# 03_Power.net
KiCad netlist of a schematic drawn in Altium Designer
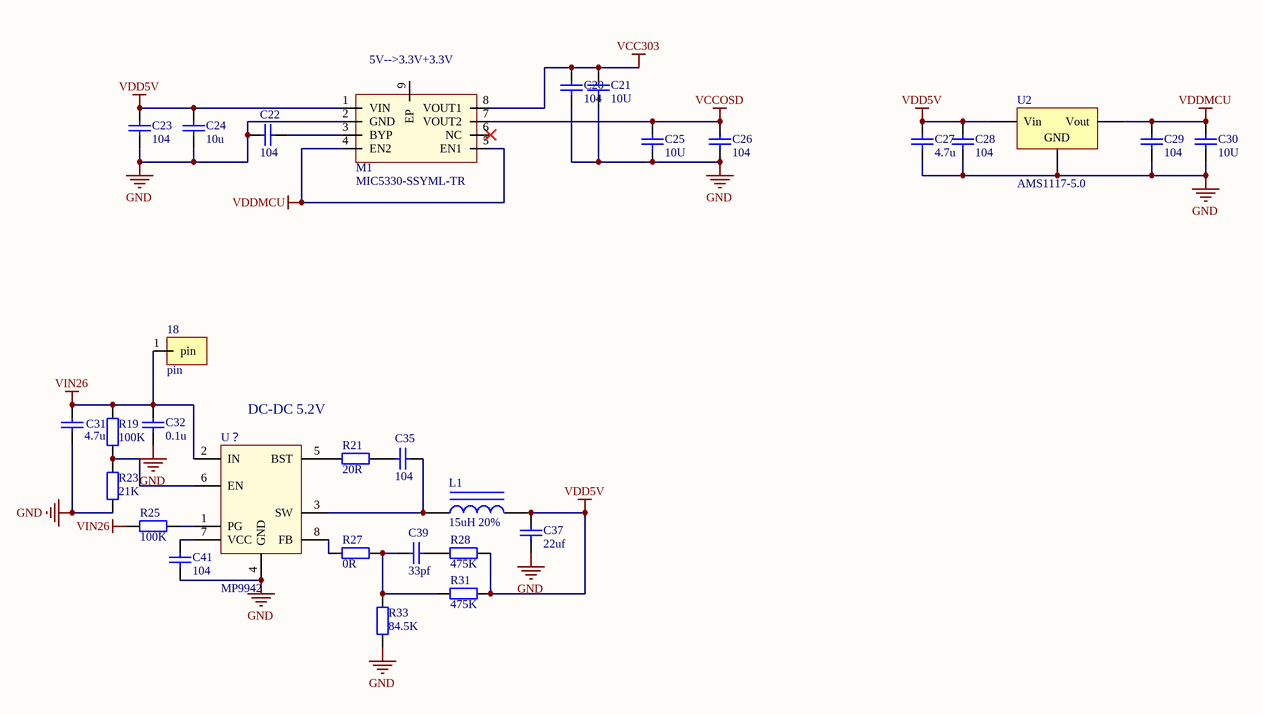
[diagram p0: 03_Power.SchDoc]

(export (version "E")
  (design (tool "Eeschema 10.0.6"))
  (components
    (comp (ref "18") (value "pin") (footprint "DIAN_0.5-1.0") (libsource (lib "My_schlib") (part "dian")))
    (comp (ref "C20")
      (value "104")
      (footprint "0402_C")
      (description "贴片电容")
      (libsource (lib "Miscellaneous Devices LC") (part "0402 100nF (104) 10% 16V"))
    )
    (comp (ref "C21")
      (value "10U")
      (footprint "0603_C")
      (description "贴片电容")
      (libsource (lib "Miscellaneous Devices LC") (part "0603 100nF (104) 10% 50V"))
    )
    (comp (ref "C22")
      (value "104")
      (footprint "0603_C")
      (description "贴片电容")
      (libsource (lib "Miscellaneous Devices LC") (part "0603 100nF (104) 10% 50V"))
    )
    (comp (ref "C23")
      (value "104")
      (footprint "0603_C")
      (description "贴片电容")
      (libsource (lib "Miscellaneous Devices LC") (part "0603 100nF (104) 10% 50V"))
    )
    (comp (ref "C24")
      (value "10u")
      (footprint "0603_C")
      (description "贴片电容")
      (libsource (lib "Miscellaneous Devices LC") (part "0603 100nF (104) 10% 50V"))
    )
    (comp (ref "C25")
      (value "10U")
      (footprint "0603_C")
      (description "贴片电容")
      (libsource (lib "Miscellaneous Devices LC") (part "0603 100nF (104) 10% 50V"))
    )
    (comp (ref "C26")
      (value "104")
      (footprint "0402_C")
      (description "贴片电容")
      (libsource (lib "Miscellaneous Devices LC") (part "0402 100nF (104) 10% 16V"))
    )
    (comp (ref "C27")
      (value "4.7u")
      (footprint "0603_C")
      (description "贴片电容")
      (libsource (lib "Miscellaneous Devices LC") (part "0603 100nF (104) 10% 50V"))
    )
    (comp (ref "C28")
      (value "104")
      (footprint "0603_C")
      (description "贴片电容")
      (libsource (lib "Miscellaneous Devices LC") (part "0603 100nF (104) 10% 50V"))
    )
    (comp (ref "C29")
      (value "104")
      (footprint "0402_C")
      (description "贴片电容")
      (libsource (lib "Miscellaneous Devices LC") (part "0402 100nF (104) 10% 16V"))
    )
    (comp (ref "C30")
      (value "10U")
      (footprint "0603_C")
      (description "贴片电容")
      (libsource (lib "Miscellaneous Devices LC") (part "0603 100nF (104) 10% 50V"))
    )
    (comp (ref "C31")
      (value "4.7u")
      (footprint "0603_C")
      (description "贴片电容")
      (libsource (lib "Miscellaneous Devices LC") (part "0603 100nF (104) 10% 50V"))
    )
    (comp (ref "C32")
      (value "0.1u")
      (footprint "0402_C")
      (description "贴片电容")
      (libsource (lib "Miscellaneous Devices LC") (part "0402 10nF (103) 10% 50V"))
    )
    (comp (ref "C35")
      (value "104")
      (footprint "0402_C")
      (description "贴片电容")
      (libsource (lib "Miscellaneous Devices LC") (part "0402 10nF (103) 10% 50V"))
    )
    (comp (ref "C37")
      (value "22uf")
      (footprint "1206_C")
      (description "贴片电容")
      (libsource (lib "Miscellaneous Devices LC") (part "1206 100nF (104) 10% 50V"))
    )
    (comp (ref "C39")
      (value "33pf")
      (footprint "0402_C")
      (description "贴片电容")
      (libsource (lib "Miscellaneous Devices LC") (part "0402 10nF (103) 10% 50V"))
    )
    (comp (ref "C41")
      (value "104")
      (footprint "0402_C")
      (description "贴片电容")
      (libsource (lib "Miscellaneous Devices LC") (part "0402 10nF (103) 10% 50V"))
    )
    (comp (ref "L1")
      (value "15uH 20%")
      (footprint "0530-L")
      (description "贴片电感")
      (libsource (lib "Miscellaneous Devices LC") (part "0402 15nH 5%"))
    )
    (comp (ref "M1")
      (value "MIC5330-SSYML-TR")
      (footprint "MIC5330-SSYML-TR")
      (description "LDO")
      (libsource (lib "My_schlib") (part "MIC5330-SSYML-TR"))
    )
    (comp (ref "R19")
      (value "100K")
      (footprint "0402_R")
      (description "贴片电阻")
      (libsource (lib "Miscellaneous Devices LC") (part "0402 10KΩ (1002) 1%"))
    )
    (comp (ref "R21")
      (value "20R")
      (footprint "0402_R")
      (description "贴片电阻")
      (libsource (lib "") (part "0402 10KΩ (1002) 1%_2"))
    )
    (comp (ref "R23")
      (value "21K")
      (footprint "0402_R")
      (description "贴片电阻")
      (libsource (lib "Miscellaneous Devices LC") (part "0402 10KΩ (1002) 1%"))
    )
    (comp (ref "R25")
      (value "100K")
      (footprint "0402_R")
      (description "贴片电阻")
      (libsource (lib "") (part "0402 10KΩ (1002) 1%_2"))
    )
    (comp (ref "R27")
      (value "0R")
      (footprint "0402_R")
      (description "贴片电阻")
      (libsource (lib "") (part "0402 10KΩ (1002) 1%_2"))
    )
    (comp (ref "R28")
      (value "475K")
      (footprint "0402_R")
      (description "贴片电阻")
      (libsource (lib "") (part "0402 10KΩ (1002) 1%_2"))
    )
    (comp (ref "R31")
      (value "475K")
      (footprint "0402_R")
      (description "贴片电阻")
      (libsource (lib "") (part "0402 10KΩ (1002) 1%_3"))
    )
    (comp (ref "R33")
      (value "84.5K")
      (footprint "0402_R")
      (description "贴片电阻")
      (libsource (lib "") (part "0402 10KΩ (1002) 1%_1"))
    )
    (comp (ref "U2")
      (value "AMS1117-5.0")
      (footprint "SOT-223")
      (description "低压差线性稳压(LDO)")
      (libsource (lib "Miscellaneous Devices LC") (part "SOT-223 AMS1117-5.0"))
    )
    (comp (ref "U？")
      (value "MP9942")
      (footprint "SOT23-8L")
      (description "DC-DC 2A 4-36V")
      (libsource (lib "My_schlib") (part "MP9942"))
    )
  )
  (nets
    (net (code "1") (name "GND") (class "Default")
      (node (ref "C20") (pin "1") (pinfunction "1_1") (pintype "passive"))
      (node (ref "C21") (pin "2") (pinfunction "2_2") (pintype "passive"))
      (node (ref "C22") (pin "2") (pinfunction "2_2") (pintype "passive"))
      (node (ref "C23") (pin "1") (pinfunction "1_1") (pintype "passive"))
      (node (ref "C24") (pin "1") (pinfunction "1_1") (pintype "passive"))
      (node (ref "C25") (pin "2") (pinfunction "2_2") (pintype "passive"))
      (node (ref "C26") (pin "1") (pinfunction "1_1") (pintype "passive"))
      (node (ref "C27") (pin "2") (pinfunction "2_2") (pintype "passive"))
      (node (ref "C28") (pin "1") (pinfunction "1_1") (pintype "passive"))
      (node (ref "C29") (pin "1") (pinfunction "1_1") (pintype "passive"))
      (node (ref "C30") (pin "2") (pinfunction "2_2") (pintype "passive"))
      (node (ref "C31") (pin "1") (pinfunction "1_1") (pintype "passive"))
      (node (ref "C32") (pin "1") (pinfunction "1_1") (pintype "passive"))
      (node (ref "C37") (pin "1") (pinfunction "1_1") (pintype "passive"))
      (node (ref "C41") (pin "1") (pinfunction "1_1") (pintype "passive"))
      (node (ref "M1") (pin "2") (pinfunction "GND_2") (pintype "passive"))
      (node (ref "R23") (pin "1") (pinfunction "1_1") (pintype "passive"))
      (node (ref "R33") (pin "2") (pinfunction "2_2") (pintype "passive"))
      (node (ref "U2") (pin "1") (pinfunction "GND_1") (pintype "passive"))
      (node (ref "U？") (pin "4") (pinfunction "GND_4") (pintype "passive"))
    )
    (net (code "2") (name "Net-(C35-Pad2)") (class "Default")
      (node (ref "C35") (pin "2") (pinfunction "2_2") (pintype "passive"))
      (node (ref "R21") (pin "1") (pinfunction "1_1") (pintype "passive"))
    )
    (net (code "3") (name "Net-(C39-Pad1)") (class "Default")
      (node (ref "C39") (pin "1") (pinfunction "1_1") (pintype "passive"))
      (node (ref "R28") (pin "2") (pinfunction "2_2") (pintype "passive"))
    )
    (net (code "4") (name "Net-(C39-Pad2)") (class "Default")
      (node (ref "C39") (pin "2") (pinfunction "2_2") (pintype "passive"))
      (node (ref "R27") (pin "1") (pinfunction "1_1") (pintype "passive"))
      (node (ref "R31") (pin "1") (pinfunction "1_1") (pintype "passive"))
      (node (ref "R33") (pin "1") (pinfunction "1_1") (pintype "passive"))
    )
    (net (code "5") (name "Net-(M1-BYP)") (class "Default")
      (node (ref "C22") (pin "1") (pinfunction "1_1") (pintype "passive"))
      (node (ref "M1") (pin "3") (pinfunction "BYP_3") (pintype "passive"))
    )
    (net (code "6") (name "Net-(U？-BST)") (class "Default")
      (node (ref "R21") (pin "2") (pinfunction "2_2") (pintype "passive"))
      (node (ref "U？") (pin "5") (pinfunction "BST_5") (pintype "passive"))
    )
    (net (code "7") (name "Net-(U？-EN)") (class "Default")
      (node (ref "R19") (pin "1") (pinfunction "1_1") (pintype "passive"))
      (node (ref "R23") (pin "2") (pinfunction "2_2") (pintype "passive"))
      (node (ref "U？") (pin "6") (pinfunction "EN_6") (pintype "passive"))
    )
    (net (code "8") (name "Net-(U？-FB)") (class "Default")
      (node (ref "R27") (pin "2") (pinfunction "2_2") (pintype "passive"))
      (node (ref "U？") (pin "8") (pinfunction "FB_8") (pintype "passive"))
    )
    (net (code "9") (name "Net-(U？-PG)") (class "Default")
      (node (ref "R25") (pin "1") (pinfunction "1_1") (pintype "passive"))
      (node (ref "U？") (pin "1") (pinfunction "PG_1") (pintype "passive"))
    )
    (net (code "10") (name "Net-(U？-SW)") (class "Default")
      (node (ref "C35") (pin "1") (pinfunction "1_1") (pintype "passive"))
      (node (ref "L1") (pin "1") (pinfunction "1_1") (pintype "passive"))
      (node (ref "U？") (pin "3") (pinfunction "SW_3") (pintype "passive"))
    )
    (net (code "11") (name "Net-(U？-VCC)") (class "Default")
      (node (ref "C41") (pin "2") (pinfunction "2_2") (pintype "passive"))
      (node (ref "U？") (pin "7") (pinfunction "VCC_7") (pintype "passive"))
    )
    (net (code "12") (name "VCC303") (class "Default")
      (node (ref "C20") (pin "2") (pinfunction "2_2") (pintype "passive"))
      (node (ref "C21") (pin "1") (pinfunction "1_1") (pintype "passive"))
      (node (ref "M1") (pin "8") (pinfunction "VOUT1_8") (pintype "passive"))
    )
    (net (code "13") (name "VCCOSD") (class "Default")
      (node (ref "C25") (pin "1") (pinfunction "1_1") (pintype "passive"))
      (node (ref "C26") (pin "2") (pinfunction "2_2") (pintype "passive"))
      (node (ref "M1") (pin "7") (pinfunction "VOUT2_7") (pintype "passive"))
    )
    (net (code "14") (name "VDD5V") (class "Default")
      (node (ref "C23") (pin "2") (pinfunction "2_2") (pintype "passive"))
      (node (ref "C24") (pin "2") (pinfunction "2_2") (pintype "passive"))
      (node (ref "C27") (pin "1") (pinfunction "1_1") (pintype "passive"))
      (node (ref "C28") (pin "2") (pinfunction "2_2") (pintype "passive"))
      (node (ref "C37") (pin "2") (pinfunction "2_2") (pintype "passive"))
      (node (ref "L1") (pin "2") (pinfunction "2_2") (pintype "passive"))
      (node (ref "M1") (pin "1") (pinfunction "VIN_1") (pintype "passive"))
      (node (ref "R28") (pin "1") (pinfunction "1_1") (pintype "passive"))
      (node (ref "R31") (pin "2") (pinfunction "2_2") (pintype "passive"))
      (node (ref "U2") (pin "3") (pinfunction "Vin_3") (pintype "passive"))
    )
    (net (code "15") (name "VDDMCU") (class "Default")
      (node (ref "C29") (pin "2") (pinfunction "2_2") (pintype "passive"))
      (node (ref "C30") (pin "1") (pinfunction "1_1") (pintype "passive"))
      (node (ref "M1") (pin "4") (pinfunction "EN2_4") (pintype "passive"))
      (node (ref "M1") (pin "5") (pinfunction "EN1_5") (pintype "passive"))
      (node (ref "U2") (pin "2") (pinfunction "Vout_2") (pintype "passive"))
    )
    (net (code "16") (name "VIN26") (class "Default")
      (node (ref "18") (pin "1") (pinfunction "pin_1") (pintype "passive"))
      (node (ref "C31") (pin "2") (pinfunction "2_2") (pintype "passive"))
      (node (ref "C32") (pin "2") (pinfunction "2_2") (pintype "passive"))
      (node (ref "R19") (pin "2") (pinfunction "2_2") (pintype "passive"))
      (node (ref "R25") (pin "2") (pinfunction "2_2") (pintype "passive"))
      (node (ref "U？") (pin "2") (pinfunction "IN_2") (pintype "passive"))
    )
    (net (code "17") (name "unconnected-(M1-EP-Pad9)") (class "Default")
      (node (ref "M1") (pin "9") (pinfunction "EP_9") (pintype "passive"))
    )
    (net (code "18") (name "unconnected-(M1-NC-Pad6)") (class "Default")
      (node (ref "M1") (pin "6") (pinfunction "NC_6") (pintype "passive+no_connect"))
    )
  )
)
